# S2_-_SWITCHES.net
KiCad netlist of a schematic drawn in Altium Designer
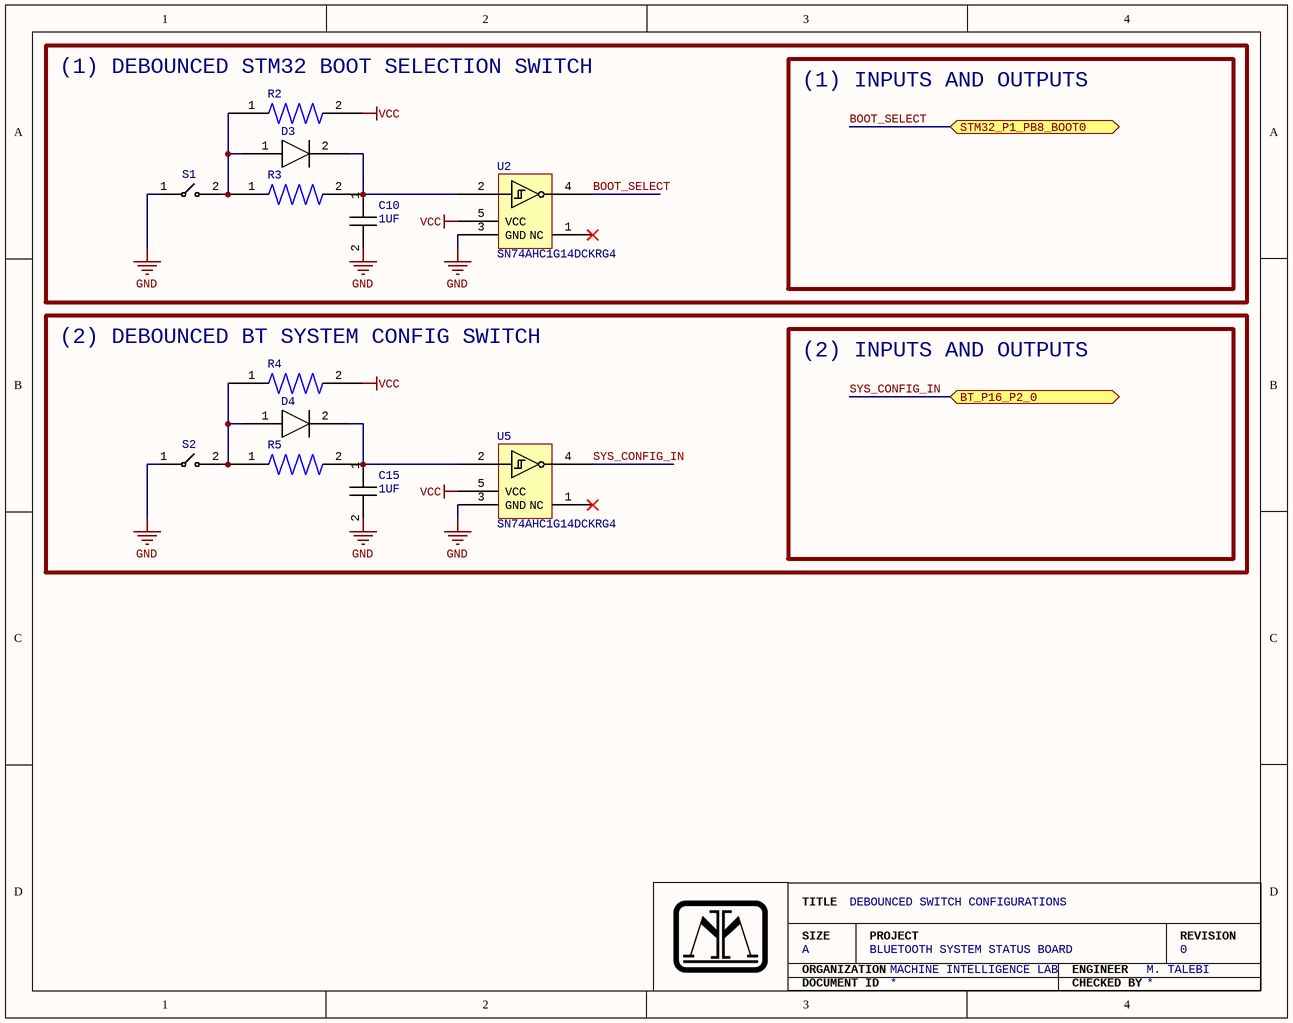
[diagram p0: S2 - SWITCHES.SchDoc]

(export (version "E")
  (design (tool "Eeschema 10.0.6"))
  (components
    (comp (ref "C10")
      (value "1UF")
      (footprint "CL10A105KQ8NNNC")
      (description "CAP CER 1UF 6.3V X5R 0603")
      (fields (field (name "TOLERANCE") "±10%"))
      (libsource (lib "Master") (part "CL10A105KQ8NNNC"))
    )
    (comp (ref "C15")
      (value "1UF")
      (footprint "CL10A105KQ8NNNC")
      (description "CAP CER 1UF 6.3V X5R 0603")
      (fields (field (name "TOLERANCE") "±10%"))
      (libsource (lib "Master") (part "CL10A105KQ8NNNC"))
    )
    (comp (ref "D3")
      (value "RS1K-13-F")
      (footprint "RS1K-13-F")
      (description "DIODE GEN PURP 800V 1A SMA")
      (libsource (lib "Master") (part "RS1K-13-F"))
    )
    (comp (ref "D4")
      (value "RS1K-13-F")
      (footprint "RS1K-13-F")
      (description "DIODE GEN PURP 800V 1A SMA")
      (libsource (lib "Master") (part "RS1K-13-F"))
    )
    (comp (ref "R2")
      (value "RT1206BRD0740KL")
      (footprint "RT1206BRD0740KL")
      (description "RES SMD 40K OHM 0.1% 1/4W 1206")
      (fields (field (name "TOLERANCE") "±0.1%"))
      (libsource (lib "Master") (part "RT1206BRD0740KL"))
    )
    (comp (ref "R3")
      (value "RT1206BRD0740KL")
      (footprint "RT1206BRD0740KL")
      (description "RES SMD 40K OHM 0.1% 1/4W 1206")
      (fields (field (name "TOLERANCE") "±0.1%"))
      (libsource (lib "Master") (part "RT1206BRD0740KL"))
    )
    (comp (ref "R4")
      (value "RT1206BRD0740KL")
      (footprint "RT1206BRD0740KL")
      (description "RES SMD 40K OHM 0.1% 1/4W 1206")
      (fields (field (name "TOLERANCE") "±0.1%"))
      (libsource (lib "Master") (part "RT1206BRD0740KL"))
    )
    (comp (ref "R5")
      (value "RT1206BRD0740KL")
      (footprint "RT1206BRD0740KL")
      (description "RES SMD 40K OHM 0.1% 1/4W 1206")
      (fields (field (name "TOLERANCE") "±0.1%"))
      (libsource (lib "Master") (part "RT1206BRD0740KL"))
    )
    (comp (ref "S1")
      (value "L101011MS02Q")
      (footprint "L101011MS02Q")
      (description "SWITCH SLIDE SPST 4A 125V")
      (libsource (lib "Master") (part "L101011MS02Q"))
    )
    (comp (ref "S2")
      (value "L101011MS02Q")
      (footprint "L101011MS02Q")
      (description "SWITCH SLIDE SPST 4A 125V")
      (libsource (lib "Master") (part "L101011MS02Q"))
    )
    (comp (ref "U2")
      (value "SN74AHC1G14DCKRG4")
      (footprint "SN74AHC1G14DCKRG4")
      (description "IC INVERT SCHMITT 1CH 1IN SC70")
      (libsource (lib "Master") (part "SN74AHC1G14DCKRG4"))
    )
    (comp (ref "U5")
      (value "SN74AHC1G14DCKRG4")
      (footprint "SN74AHC1G14DCKRG4")
      (description "IC INVERT SCHMITT 1CH 1IN SC70")
      (libsource (lib "Master") (part "SN74AHC1G14DCKRG4"))
    )
  )
  (nets
    (net (code "1") (name "/BOOT_SELECT") (class "Default")
      (node (ref "U2") (pin "4") (pinfunction "4_4") (pintype "passive"))
    )
    (net (code "2") (name "/SYS_CONFIG_IN") (class "Default")
      (node (ref "U5") (pin "4") (pinfunction "4_4") (pintype "passive"))
    )
    (net (code "3") (name "GND") (class "Default")
      (node (ref "C10") (pin "2") (pinfunction "2_2") (pintype "passive"))
      (node (ref "C15") (pin "2") (pinfunction "2_2") (pintype "passive"))
      (node (ref "S1") (pin "1") (pinfunction "1_1") (pintype "passive"))
      (node (ref "S2") (pin "1") (pinfunction "1_1") (pintype "passive"))
      (node (ref "U2") (pin "3") (pinfunction "GND_3") (pintype "passive"))
      (node (ref "U5") (pin "3") (pinfunction "GND_3") (pintype "passive"))
    )
    (net (code "4") (name "Net-(D3-+)") (class "Default")
      (node (ref "C10") (pin "1") (pinfunction "1_1") (pintype "passive"))
      (node (ref "D3") (pin "2") (pinfunction "+_2") (pintype "passive"))
      (node (ref "R3") (pin "2") (pinfunction "2_2") (pintype "passive"))
      (node (ref "U2") (pin "2") (pinfunction "2_2") (pintype "passive"))
    )
    (net (code "5") (name "Net-(D3--)") (class "Default")
      (node (ref "D3") (pin "1") (pinfunction "-_1") (pintype "passive"))
      (node (ref "R2") (pin "1") (pinfunction "1_1") (pintype "passive"))
      (node (ref "R3") (pin "1") (pinfunction "1_1") (pintype "passive"))
      (node (ref "S1") (pin "2") (pinfunction "2_2") (pintype "passive"))
    )
    (net (code "6") (name "Net-(D4-+)") (class "Default")
      (node (ref "C15") (pin "1") (pinfunction "1_1") (pintype "passive"))
      (node (ref "D4") (pin "2") (pinfunction "+_2") (pintype "passive"))
      (node (ref "R5") (pin "2") (pinfunction "2_2") (pintype "passive"))
      (node (ref "U5") (pin "2") (pinfunction "2_2") (pintype "passive"))
    )
    (net (code "7") (name "Net-(D4--)") (class "Default")
      (node (ref "D4") (pin "1") (pinfunction "-_1") (pintype "passive"))
      (node (ref "R4") (pin "1") (pinfunction "1_1") (pintype "passive"))
      (node (ref "R5") (pin "1") (pinfunction "1_1") (pintype "passive"))
      (node (ref "S2") (pin "2") (pinfunction "2_2") (pintype "passive"))
    )
    (net (code "8") (name "VCC") (class "Default")
      (node (ref "R2") (pin "2") (pinfunction "2_2") (pintype "passive"))
      (node (ref "R4") (pin "2") (pinfunction "2_2") (pintype "passive"))
      (node (ref "U2") (pin "5") (pinfunction "VCC_5") (pintype "passive"))
      (node (ref "U5") (pin "5") (pinfunction "VCC_5") (pintype "passive"))
    )
    (net (code "9") (name "unconnected-(U2-NC-Pad1)") (class "Default")
      (node (ref "U2") (pin "1") (pinfunction "NC_1") (pintype "passive+no_connect"))
    )
    (net (code "10") (name "unconnected-(U5-NC-Pad1)") (class "Default")
      (node (ref "U5") (pin "1") (pinfunction "NC_1") (pintype "passive+no_connect"))
    )
  )
)
